# ADXL343_Rev_B.net
KiCad netlist of a schematic drawn in EAGLE
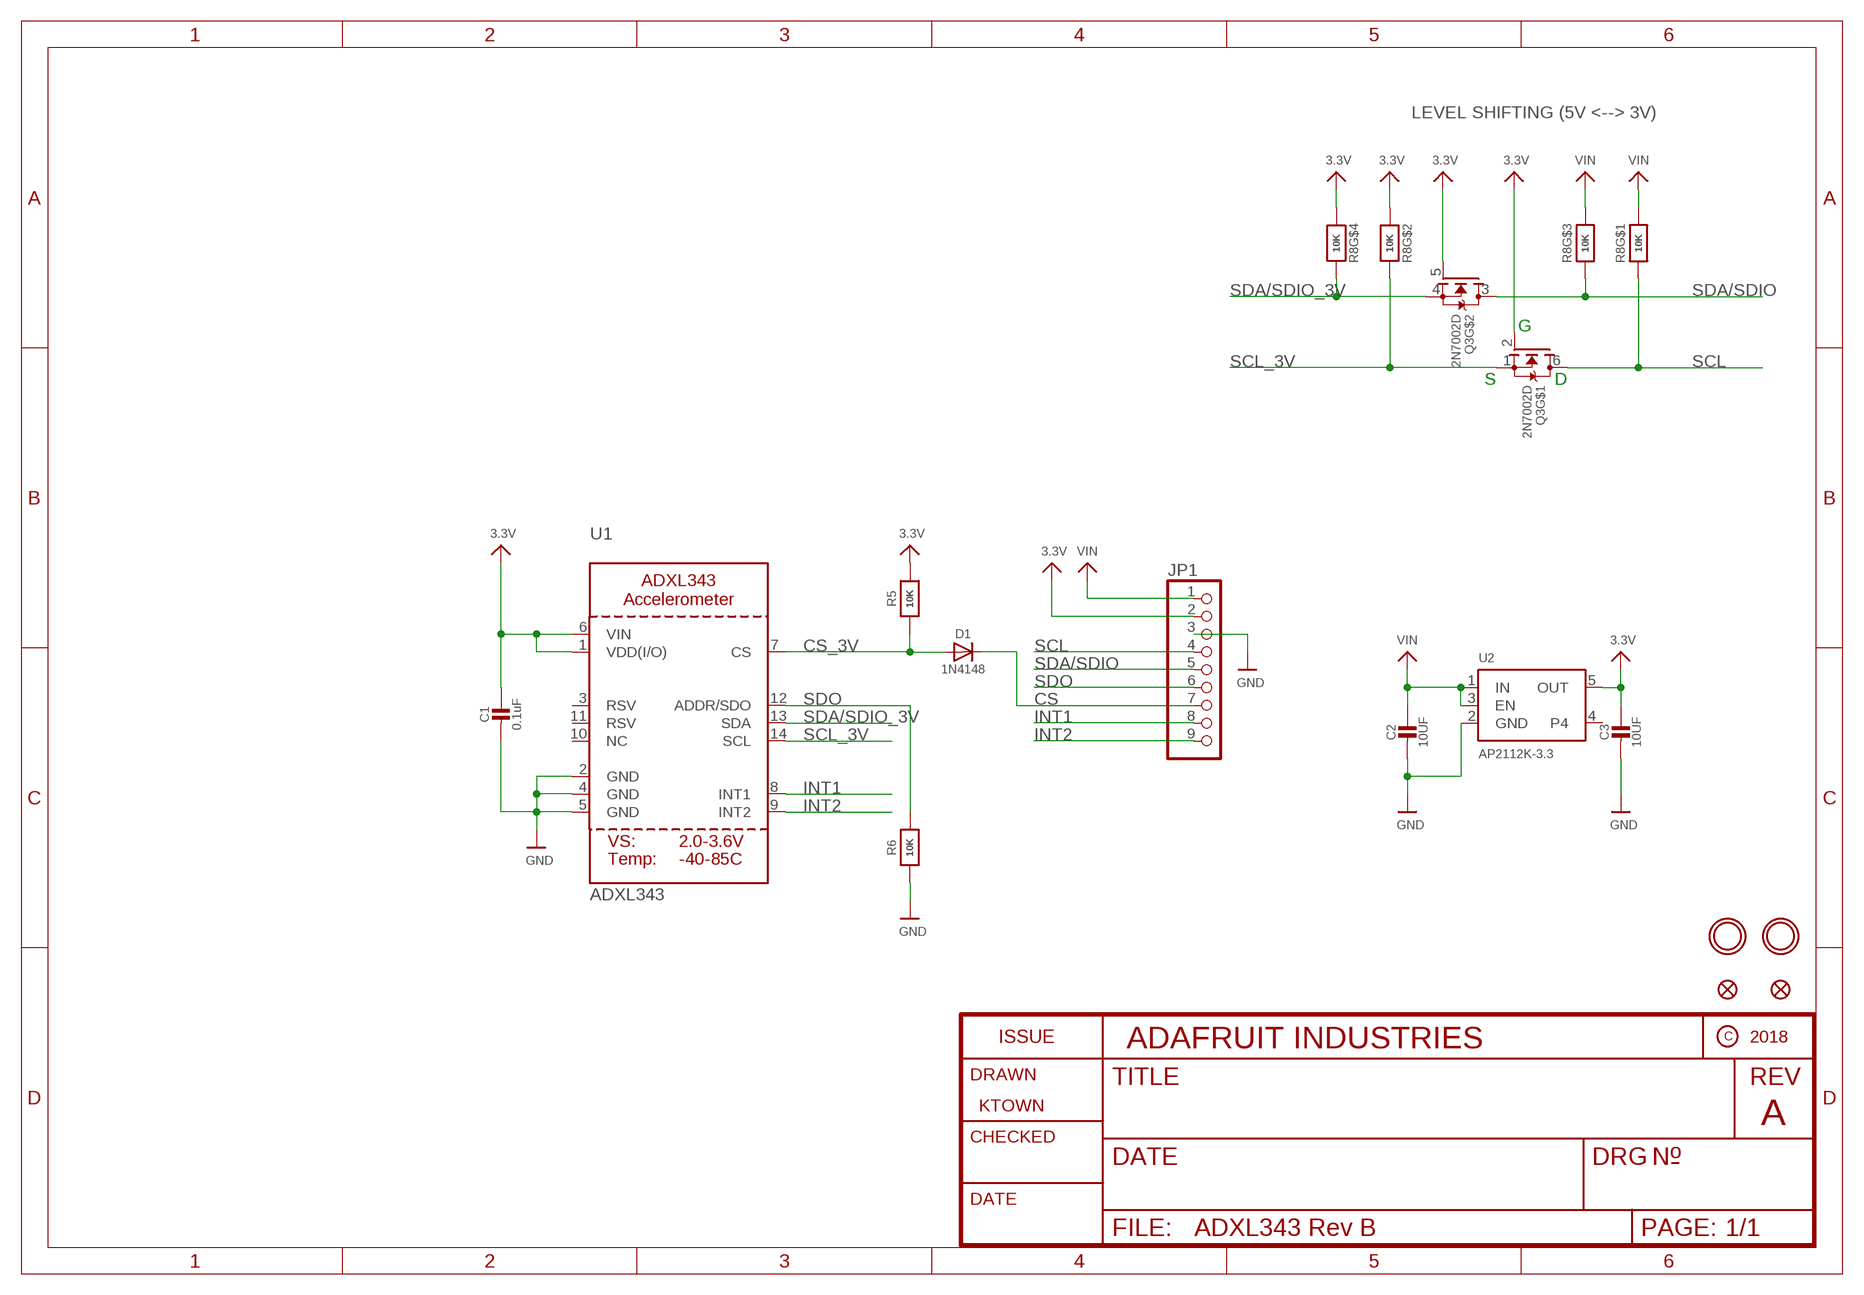
[diagram p0: schematic, sheet 1]

(export (version "E")
  (design (tool "Eeschema 10.0.6"))
  (components
    (comp (ref "C1")
      (value "0.1uF")
      (footprint "eagle-import:0603-NO")
      (libsource (lib "eagle-import") (part "CAP_CERAMIC0603_NO"))
    )
    (comp (ref "C2")
      (value "10UF")
      (footprint "eagle-import:0805-NO")
      (libsource (lib "eagle-import") (part "CAP_CERAMIC0805-NOOUTLINE"))
    )
    (comp (ref "C3")
      (value "10UF")
      (footprint "eagle-import:0805-NO")
      (libsource (lib "eagle-import") (part "CAP_CERAMIC0805-NOOUTLINE"))
    )
    (comp (ref "D1")
      (value "1N4148")
      (footprint "eagle-import:SOD-323")
      (libsource (lib "eagle-import") (part "DIODESOD-323"))
    )
    (comp (ref "JP1")
      (value "HEADER-1X970MIL")
      (footprint "eagle-import:1X09_ROUND_70")
      (libsource (lib "eagle-import") (part "HEADER-1X970MIL"))
    )
    (comp (ref "Q3")
      (value "2N7002D")
      (footprint "eagle-import:SOT363")
      (libsource (lib "eagle-import") (part "MOSFET-N_DUAL"))
    )
    (comp (ref "R5")
      (value "10K")
      (footprint "eagle-import:0603-NO")
      (libsource (lib "eagle-import") (part "RESISTOR_0603_NOOUT"))
    )
    (comp (ref "R6")
      (value "10K")
      (footprint "eagle-import:0603-NO")
      (libsource (lib "eagle-import") (part "RESISTOR_0603_NOOUT"))
    )
    (comp (ref "R8")
      (value "10K")
      (footprint "eagle-import:RESPACK_4X0603")
      (libsource (lib "eagle-import") (part "RESISTOR_4PACK"))
    )
    (comp (ref "U$1")
      (value "FIDUCIAL_1MM")
      (footprint "eagle-import:FIDUCIAL_1MM")
      (libsource (lib "eagle-import") (part "FIDUCIAL_1MM"))
    )
    (comp (ref "U$3")
      (value "FIDUCIAL_1MM")
      (footprint "eagle-import:FIDUCIAL_1MM")
      (libsource (lib "eagle-import") (part "FIDUCIAL_1MM"))
    )
    (comp (ref "U$4")
      (value "MOUNTINGHOLE2.5")
      (footprint "eagle-import:MOUNTINGHOLE_2.5_PLATED")
      (libsource (lib "eagle-import") (part "MOUNTINGHOLE2.5"))
    )
    (comp (ref "U$6")
      (value "MOUNTINGHOLE2.5")
      (footprint "eagle-import:MOUNTINGHOLE_2.5_PLATED")
      (libsource (lib "eagle-import") (part "MOUNTINGHOLE2.5"))
    )
    (comp (ref "U1")
      (value "ADXL343")
      (footprint "eagle-import:LGA14")
      (libsource (lib "eagle-import") (part "ACCEL_ADXL343"))
    )
    (comp (ref "U2")
      (value "AP2112K-3.3")
      (footprint "eagle-import:SOT23-5")
      (libsource (lib "eagle-import") (part "VREG_SOT23-5"))
    )
  )
  (nets
    (net (code "1") (name "/CS") (class "Default")
      (node (ref "D1") (pin "C") (pinfunction "C_C") (pintype "passive"))
      (node (ref "JP1") (pin "7") (pinfunction "7_7") (pintype "passive"))
    )
    (net (code "2") (name "/CS_3V") (class "Default")
      (node (ref "D1") (pin "A") (pinfunction "A_A") (pintype "passive"))
      (node (ref "R5") (pin "1") (pinfunction "1_1") (pintype "passive"))
      (node (ref "U1") (pin "7") (pinfunction "CS_7") (pintype "bidirectional"))
    )
    (net (code "3") (name "/INT1") (class "Default")
      (node (ref "JP1") (pin "8") (pinfunction "8_8") (pintype "passive"))
      (node (ref "U1") (pin "8") (pinfunction "INT1_8") (pintype "bidirectional"))
    )
    (net (code "4") (name "/INT2") (class "Default")
      (node (ref "JP1") (pin "9") (pinfunction "9_9") (pintype "passive"))
      (node (ref "U1") (pin "9") (pinfunction "INT2_9") (pintype "bidirectional"))
    )
    (net (code "5") (name "/SCL") (class "Default")
      (node (ref "JP1") (pin "4") (pinfunction "4_4") (pintype "passive"))
      (node (ref "Q3") (pin "6") (pinfunction "D_6") (pintype "bidirectional"))
      (node (ref "R8") (pin "8") (pinfunction "2_8") (pintype "passive"))
    )
    (net (code "6") (name "/SCL_3V") (class "Default")
      (node (ref "Q3") (pin "1") (pinfunction "S_1") (pintype "bidirectional"))
      (node (ref "R8") (pin "7") (pinfunction "2_7") (pintype "passive"))
      (node (ref "U1") (pin "14") (pinfunction "SCL_14") (pintype "bidirectional"))
    )
    (net (code "7") (name "/SDA{slash}SDIO") (class "Default")
      (node (ref "JP1") (pin "5") (pinfunction "5_5") (pintype "passive"))
      (node (ref "Q3") (pin "3") (pinfunction "D_3") (pintype "bidirectional"))
      (node (ref "R8") (pin "6") (pinfunction "2_6") (pintype "passive"))
    )
    (net (code "8") (name "/SDA{slash}SDIO_3V") (class "Default")
      (node (ref "Q3") (pin "4") (pinfunction "S_4") (pintype "bidirectional"))
      (node (ref "R8") (pin "5") (pinfunction "2_5") (pintype "passive"))
      (node (ref "U1") (pin "13") (pinfunction "SDA_13") (pintype "bidirectional"))
    )
    (net (code "9") (name "/SDO") (class "Default")
      (node (ref "JP1") (pin "6") (pinfunction "6_6") (pintype "passive"))
      (node (ref "R6") (pin "2") (pinfunction "2_2") (pintype "passive"))
      (node (ref "U1") (pin "12") (pinfunction "ADDR/SDO_12") (pintype "bidirectional"))
    )
    (net (code "10") (name "3.3V") (class "Default")
      (node (ref "C1") (pin "1") (pinfunction "1_1") (pintype "passive"))
      (node (ref "C3") (pin "1") (pinfunction "1_1") (pintype "passive"))
      (node (ref "JP1") (pin "2") (pinfunction "2_2") (pintype "passive"))
      (node (ref "Q3") (pin "2") (pinfunction "G_2") (pintype "bidirectional"))
      (node (ref "Q3") (pin "5") (pinfunction "G_5") (pintype "bidirectional"))
      (node (ref "R5") (pin "2") (pinfunction "2_2") (pintype "passive"))
      (node (ref "R8") (pin "2") (pinfunction "1_2") (pintype "passive"))
      (node (ref "R8") (pin "4") (pinfunction "1_4") (pintype "passive"))
      (node (ref "U1") (pin "1") (pinfunction "VDD(I/O)_1") (pintype "bidirectional"))
      (node (ref "U1") (pin "6") (pinfunction "VIN_6") (pintype "bidirectional"))
      (node (ref "U2") (pin "5") (pinfunction "OUT_5") (pintype "power_in"))
    )
    (net (code "11") (name "GND") (class "Default")
      (node (ref "C1") (pin "2") (pinfunction "2_2") (pintype "passive"))
      (node (ref "C2") (pin "2") (pinfunction "2_2") (pintype "passive"))
      (node (ref "C3") (pin "2") (pinfunction "2_2") (pintype "passive"))
      (node (ref "JP1") (pin "3") (pinfunction "3_3") (pintype "passive"))
      (node (ref "R6") (pin "1") (pinfunction "1_1") (pintype "passive"))
      (node (ref "U1") (pin "2") (pinfunction "GND_2") (pintype "bidirectional"))
      (node (ref "U1") (pin "4") (pinfunction "GND_4") (pintype "bidirectional"))
      (node (ref "U1") (pin "5") (pinfunction "GND_5") (pintype "bidirectional"))
      (node (ref "U2") (pin "2") (pinfunction "GND_2") (pintype "power_in"))
    )
    (net (code "12") (name "VIN") (class "Default")
      (node (ref "C2") (pin "1") (pinfunction "1_1") (pintype "passive"))
      (node (ref "JP1") (pin "1") (pinfunction "1_1") (pintype "passive"))
      (node (ref "R8") (pin "1") (pinfunction "1_1") (pintype "passive"))
      (node (ref "R8") (pin "3") (pinfunction "1_3") (pintype "passive"))
      (node (ref "U2") (pin "1") (pinfunction "IN_1") (pintype "power_in"))
      (node (ref "U2") (pin "3") (pinfunction "EN_3") (pintype "input"))
    )
    (net (code "13") (name "unconnected-(U1-NC-Pad10)") (class "Default")
      (node (ref "U1") (pin "10") (pinfunction "NC_10") (pintype "bidirectional"))
    )
    (net (code "14") (name "unconnected-(U1-RSV-Pad3)") (class "Default")
      (node (ref "U1") (pin "3") (pinfunction "RSV_3") (pintype "bidirectional"))
    )
    (net (code "15") (name "unconnected-(U1-RSV-Pad11)") (class "Default")
      (node (ref "U1") (pin "11") (pinfunction "RSV_11") (pintype "bidirectional"))
    )
    (net (code "16") (name "unconnected-(U2-P4-Pad4)") (class "Default")
      (node (ref "U2") (pin "4") (pinfunction "P4_4") (pintype "bidirectional"))
    )
  )
)
